# 02-RCB_Header.net
KiCad netlist of a schematic drawn in Altium Designer
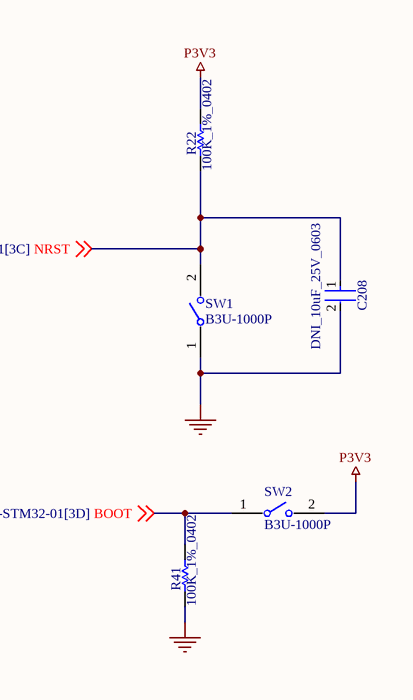
[diagram p0: 02-RCB_Header.SchDoc]

(export (version "E")
  (design (tool "Eeschema 10.0.6"))
  (components
    (comp (ref "C208")
      (value "DNI_10uF_25V_0603")
      (footprint "FP-CL10-IPC_C")
      (description "Cap Ceramic 10uF 25V X5R ±20% Pad SMD 0603 +85°C T/R")
      (fields (field (name "TOLERANCE") "20%"))
      (libsource (lib "Altium Content Vault") (part "b4654b650e69147ec39a6b967a45e02"))
    )
    (comp (ref "R22")
      (value "100K_1%_0402")
      (footprint "RESC1005X40X25ML05T10")
      (fields (field (name "MANUFACTURER") "Yageo") (field (name "PART NUMBER") "RC0402FR-13100KL"))
      (libsource (lib "Altium Content Vault") (part "RES"))
    )
    (comp (ref "R41")
      (value "100K_1%_0402")
      (footprint "RESC1005X40X25ML05T10")
      (fields (field (name "MANUFACTURER") "Yageo") (field (name "PART NUMBER") "RC0402FR-13100KL"))
      (libsource (lib "Altium Content Vault") (part "RES"))
    )
    (comp (ref "SW1")
      (value "B3U-1000P")
      (footprint "FP-B3U-1000P-MFG")
      (description "SWITCH TACTILE SPST-NO 0.05A 12V")
      (libsource (lib "Altium Content Vault") (part "ae622034201233ca1abcedc05908f33"))
    )
    (comp (ref "SW2")
      (value "B3U-1000P")
      (footprint "FP-B3U-1000P-MFG")
      (description "SWITCH TACTILE SPST-NO 0.05A 12V")
      (libsource (lib "Altium Content Vault") (part "ae622034201233ca1abcedc05908f33"))
    )
  )
  (nets
    (net (code "1") (name "BOOT") (class "Default")
      (node (ref "R41") (pin "2") (pinfunction "2_2") (pintype "passive"))
      (node (ref "SW2") (pin "1") (pinfunction "1_1") (pintype "passive"))
    )
    (net (code "2") (name "GND") (class "Default")
      (node (ref "C208") (pin "2") (pinfunction "2_2") (pintype "passive"))
      (node (ref "R41") (pin "1") (pinfunction "1_1") (pintype "passive"))
      (node (ref "SW1") (pin "1") (pinfunction "1_1") (pintype "passive"))
    )
    (net (code "3") (name "NRST") (class "Default")
      (node (ref "C208") (pin "1") (pinfunction "1_1") (pintype "passive"))
      (node (ref "R22") (pin "1") (pinfunction "1_1") (pintype "passive"))
      (node (ref "SW1") (pin "2") (pinfunction "2_2") (pintype "passive"))
    )
    (net (code "4") (name "P3V3") (class "Default")
      (node (ref "R22") (pin "2") (pinfunction "2_2") (pintype "passive"))
      (node (ref "SW2") (pin "2") (pinfunction "2_2") (pintype "passive"))
    )
  )
)
